# UV_MONITOR_V2.net
KiCad netlist of a schematic drawn in EAGLE
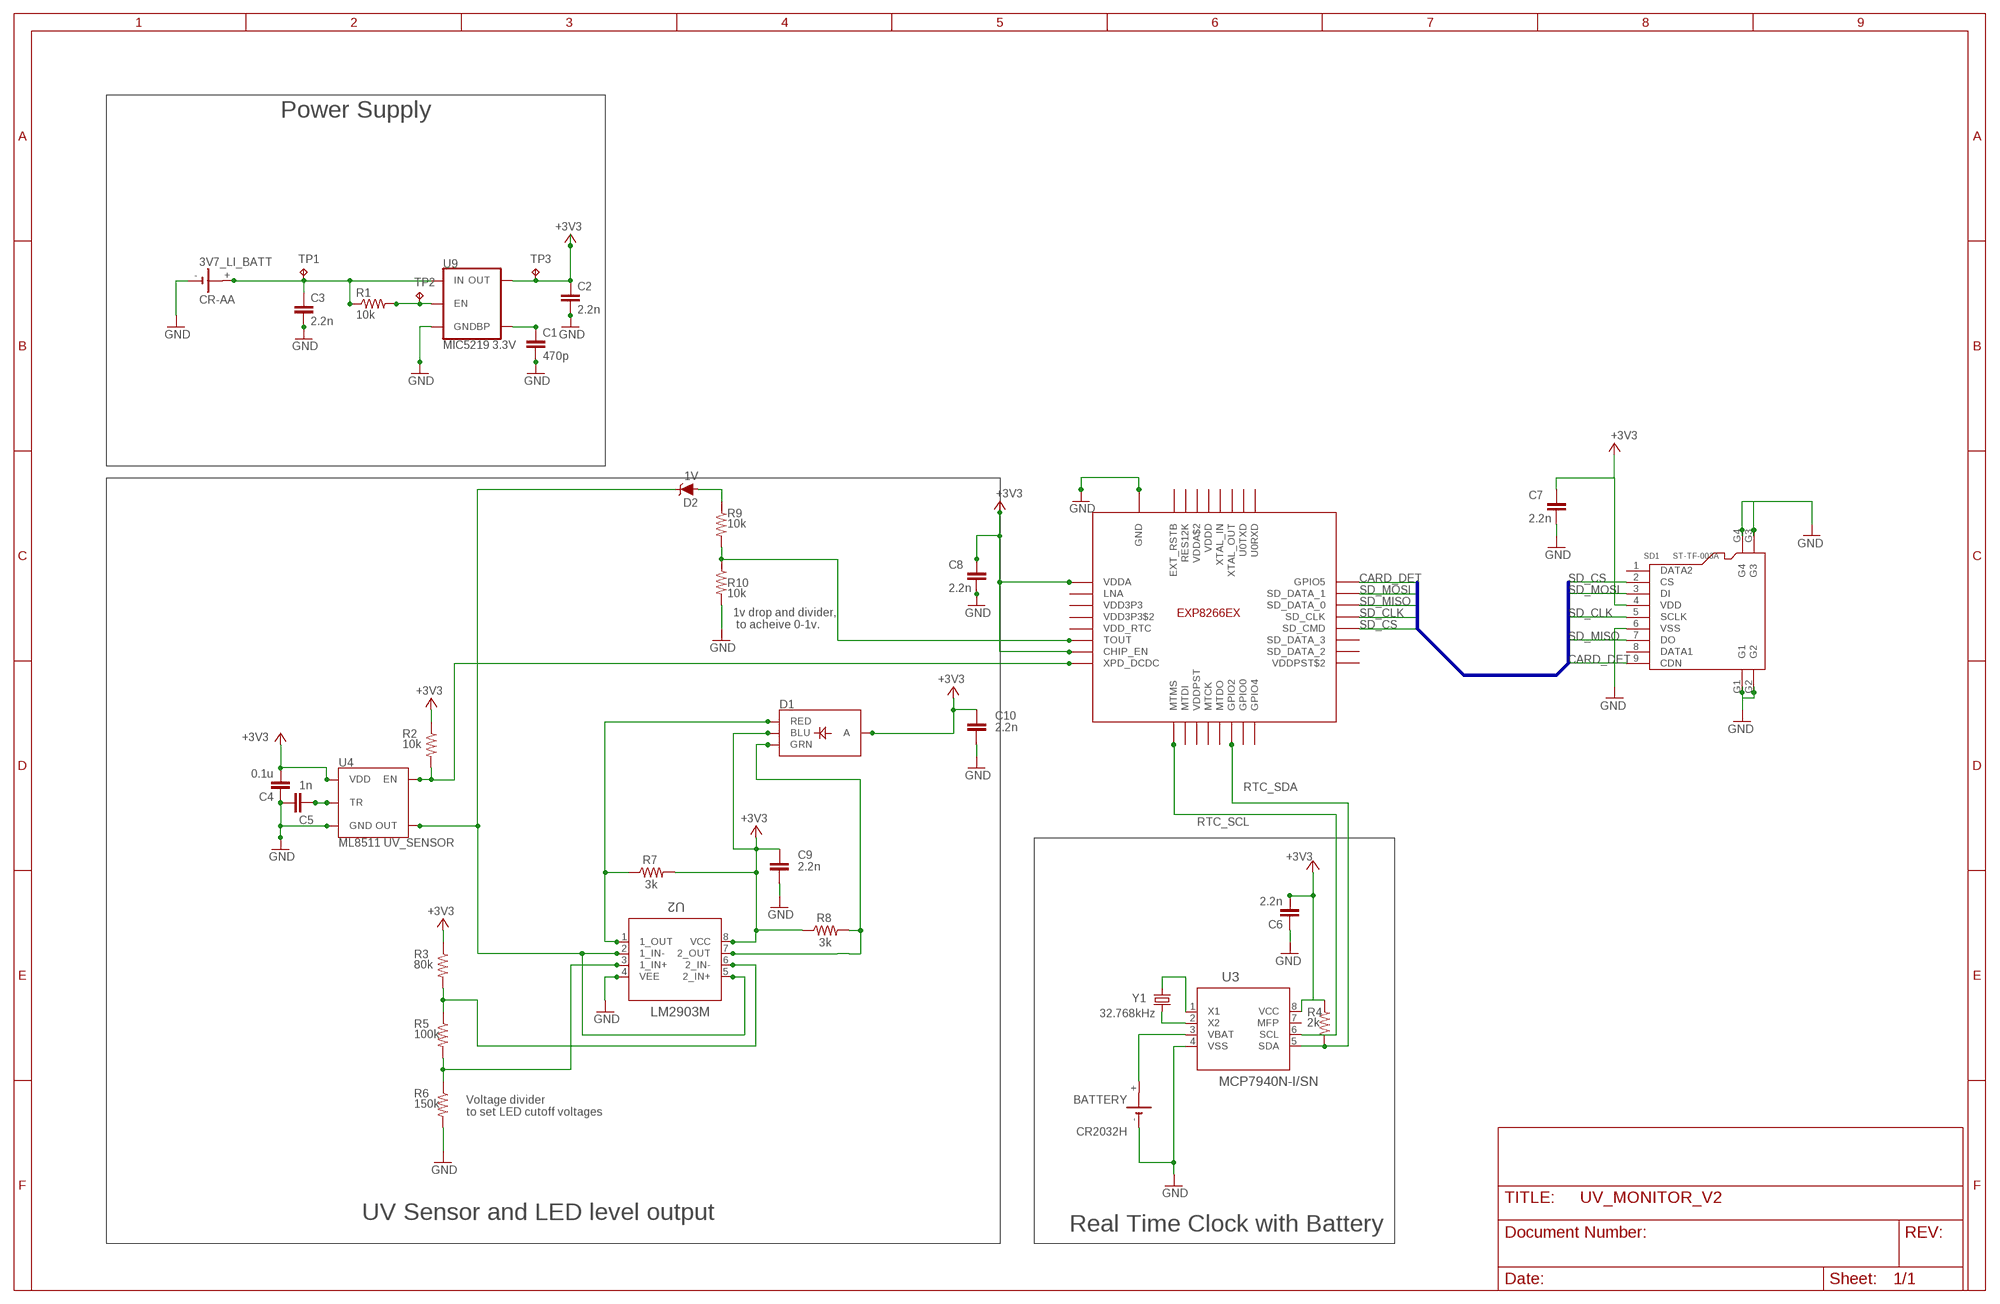
[diagram p0: schematic, sheet 1]

(export (version "E")
  (design (tool "Eeschema 10.0.6"))
  (components
    (comp (ref "3V7_LI_BATT")
      (value "CR-AA")
      (footprint "eagle-import:CRAA")
      (libsource (lib "eagle-import") (part "CR-AA"))
    )
    (comp (ref "BATTERY")
      (value "CR2032H")
      (footprint "eagle-import:CR2032H")
      (libsource (lib "eagle-import") (part "CR2032H"))
    )
    (comp (ref "C1")
      (value "470p")
      (footprint "eagle-import:C0805")
      (libsource (lib "eagle-import") (part "C-EUC0805"))
    )
    (comp (ref "C2")
      (value "2.2n")
      (footprint "eagle-import:C0805")
      (libsource (lib "eagle-import") (part "C-EUC0805"))
    )
    (comp (ref "C3")
      (value "2.2n")
      (footprint "eagle-import:C0805")
      (libsource (lib "eagle-import") (part "C-EUC0805"))
    )
    (comp (ref "C4")
      (value "0.1u")
      (footprint "eagle-import:C0805")
      (libsource (lib "eagle-import") (part "C-EUC0805"))
    )
    (comp (ref "C5")
      (value "1n")
      (footprint "eagle-import:C0805")
      (libsource (lib "eagle-import") (part "C-EUC0805"))
    )
    (comp (ref "C6")
      (value "2.2n")
      (footprint "eagle-import:C0805")
      (libsource (lib "eagle-import") (part "C-EUC0805"))
    )
    (comp (ref "C7")
      (value "2.2n")
      (footprint "eagle-import:C0805")
      (libsource (lib "eagle-import") (part "C-EUC0805"))
    )
    (comp (ref "C8")
      (value "2.2n")
      (footprint "eagle-import:C0805")
      (libsource (lib "eagle-import") (part "C-EUC0805"))
    )
    (comp (ref "C9")
      (value "2.2n")
      (footprint "eagle-import:C0805")
      (libsource (lib "eagle-import") (part "C-EUC0805"))
    )
    (comp (ref "C10")
      (value "2.2n")
      (footprint "eagle-import:C0805")
      (libsource (lib "eagle-import") (part "C-EUC0805"))
    )
    (comp (ref "D1")
      (value "LED-RGB-CASMD")
      (footprint "eagle-import:LED-TRICOLOR-SMD")
      (libsource (lib "eagle-import") (part "LED-RGB-CASMD"))
    )
    (comp (ref "D2")
      (value "1V")
      (footprint "eagle-import:SOD-323")
      (libsource (lib "eagle-import") (part "DIODE-ZENER-BZT52C3V6S"))
    )
    (comp (ref "R1")
      (value "10k")
      (footprint "eagle-import:R0805")
      (libsource (lib "eagle-import") (part "R-US_R0805"))
    )
    (comp (ref "R2")
      (value "10k")
      (footprint "eagle-import:R0805")
      (libsource (lib "eagle-import") (part "R-US_R0805"))
    )
    (comp (ref "R3")
      (value "80k")
      (footprint "eagle-import:R0805")
      (libsource (lib "eagle-import") (part "R-US_R0805"))
    )
    (comp (ref "R4")
      (value "2k")
      (footprint "eagle-import:R0805")
      (libsource (lib "eagle-import") (part "R-US_R0805"))
    )
    (comp (ref "R5")
      (value "100k")
      (footprint "eagle-import:R0805")
      (libsource (lib "eagle-import") (part "R-US_R0805"))
    )
    (comp (ref "R6")
      (value "150k")
      (footprint "eagle-import:R0805")
      (libsource (lib "eagle-import") (part "R-US_R0805"))
    )
    (comp (ref "R7")
      (value "3k")
      (footprint "eagle-import:R0805")
      (libsource (lib "eagle-import") (part "R-US_R0805"))
    )
    (comp (ref "R8")
      (value "3k")
      (footprint "eagle-import:R0805")
      (libsource (lib "eagle-import") (part "R-US_R0805"))
    )
    (comp (ref "R9")
      (value "10k")
      (footprint "eagle-import:R0805")
      (libsource (lib "eagle-import") (part "R-US_R0805"))
    )
    (comp (ref "R10")
      (value "10k")
      (footprint "eagle-import:R0805")
      (libsource (lib "eagle-import") (part "R-US_R0805"))
    )
    (comp (ref "SD1")
      (value "ST-TF-003A")
      (footprint "eagle-import:MICRO-SD9+4P-SMD-16.1X14.5X1.85MM")
      (libsource (lib "eagle-import") (part "MICRO-SD-CARD-SOCKET-9P(ST-TF-003A)"))
    )
    (comp (ref "TP1")
      (value "TPPAD1-13")
      (footprint "eagle-import:P1-13")
      (libsource (lib "eagle-import") (part "TPPAD1-13"))
    )
    (comp (ref "TP2")
      (value "TPPAD1-13")
      (footprint "eagle-import:P1-13")
      (libsource (lib "eagle-import") (part "TPPAD1-13"))
    )
    (comp (ref "TP3")
      (value "TPPAD1-13")
      (footprint "eagle-import:P1-13")
      (libsource (lib "eagle-import") (part "TPPAD1-13"))
    )
    (comp (ref "U1")
      (value "ESP8266EX")
      (footprint "eagle-import:ESP8266EX")
      (libsource (lib "eagle-import") (part "ESP8266EX"))
    )
    (comp (ref "U2")
      (value "LM2903M")
      (footprint "eagle-import:M08A")
      (libsource (lib "eagle-import") (part "LM2903M"))
    )
    (comp (ref "U3")
      (value "MCP7940N-I/SN")
      (footprint "eagle-import:SOIC8-N_MC")
      (fields (field (name "MANUFACTURER_PART_NUMBER") "MCP7940NISN"))
      (libsource (lib "eagle-import") (part "MCP7940N-I/SN"))
    )
    (comp (ref "U4")
      (value "ML8511 UV_SENSOR")
      (footprint "eagle-import:ML8511")
      (libsource (lib "eagle-import") (part "ML8511"))
    )
    (comp (ref "U9")
      (value "MIC5219 3.3V")
      (footprint "eagle-import:SOT23-5")
      (libsource (lib "eagle-import") (part "V_REG_MIC52193.3V"))
    )
    (comp (ref "Y1")
      (value "32.768kHz")
      (footprint "eagle-import:CRYSTAL-SMD-2X6-CYL")
      (libsource (lib "eagle-import") (part "CRYSTAL-32.768KHZSMD-2X6"))
    )
  )
  (nets
    (net (code "1") (name "+3V3") (class "Default")
      (node (ref "C10") (pin "1") (pinfunction "1_1") (pintype "passive"))
      (node (ref "C2") (pin "1") (pinfunction "1_1") (pintype "passive"))
      (node (ref "C4") (pin "2") (pinfunction "2_2") (pintype "passive"))
      (node (ref "C6") (pin "2") (pinfunction "2_2") (pintype "passive"))
      (node (ref "C7") (pin "1") (pinfunction "1_1") (pintype "passive"))
      (node (ref "C8") (pin "1") (pinfunction "1_1") (pintype "passive"))
      (node (ref "C9") (pin "1") (pinfunction "1_1") (pintype "passive"))
      (node (ref "D1") (pin "A") (pinfunction "A_A") (pintype "bidirectional"))
      (node (ref "D1") (pin "B") (pinfunction "BLU_B") (pintype "bidirectional"))
      (node (ref "R2") (pin "1") (pinfunction "1_1") (pintype "passive"))
      (node (ref "R3") (pin "1") (pinfunction "1_1") (pintype "passive"))
      (node (ref "R4") (pin "1") (pinfunction "1_1") (pintype "passive"))
      (node (ref "R7") (pin "2") (pinfunction "2_2") (pintype "passive"))
      (node (ref "R8") (pin "1") (pinfunction "1_1") (pintype "passive"))
      (node (ref "SD1") (pin "4") (pinfunction "VDD_4") (pintype "bidirectional"))
      (node (ref "TP3") (pin "TP") (pinfunction "TP_TP") (pintype "input"))
      (node (ref "U1") (pin "CHIP_EN") (pinfunction "CHIP_EN_CHIP_EN") (pintype "bidirectional"))
      (node (ref "U1") (pin "VDDA") (pinfunction "VDDA_VDDA") (pintype "bidirectional"))
      (node (ref "U2") (pin "8") (pinfunction "VCC_8") (pintype "passive"))
      (node (ref "U3") (pin "8") (pinfunction "VCC_8") (pintype "power_in"))
      (node (ref "U4") (pin "7") (pinfunction "VDD_7") (pintype "power_in"))
      (node (ref "U9") (pin "5") (pinfunction "OUT_5") (pintype "passive"))
    )
    (net (code "2") (name "/CARD_DET") (class "Default")
      (node (ref "SD1") (pin "9") (pinfunction "CDN_9") (pintype "bidirectional"))
      (node (ref "U1") (pin "GPOIO5") (pinfunction "GPIO5_GPOIO5") (pintype "bidirectional"))
    )
    (net (code "3") (name "/RTC_SCL") (class "Default")
      (node (ref "U1") (pin "MTMS") (pinfunction "MTMS_MTMS") (pintype "bidirectional"))
      (node (ref "U3") (pin "6") (pinfunction "SCL_6") (pintype "passive"))
    )
    (net (code "4") (name "/RTC_SDA") (class "Default")
      (node (ref "R4") (pin "2") (pinfunction "2_2") (pintype "passive"))
      (node (ref "U1") (pin "GPIO2") (pinfunction "GPIO2_GPIO2") (pintype "bidirectional"))
      (node (ref "U3") (pin "5") (pinfunction "SDA_5") (pintype "bidirectional"))
    )
    (net (code "5") (name "/SD_CLK") (class "Default")
      (node (ref "SD1") (pin "5") (pinfunction "SCLK_5") (pintype "bidirectional"))
      (node (ref "U1") (pin "SD_CLK") (pinfunction "SD_CLK_SD_CLK") (pintype "bidirectional"))
    )
    (net (code "6") (name "/SD_CS") (class "Default")
      (node (ref "SD1") (pin "2") (pinfunction "CS_2") (pintype "bidirectional"))
      (node (ref "U1") (pin "SD_CMD") (pinfunction "SD_CMD_SD_CMD") (pintype "bidirectional"))
    )
    (net (code "7") (name "/SD_MISO") (class "Default")
      (node (ref "SD1") (pin "7") (pinfunction "DO_7") (pintype "bidirectional"))
      (node (ref "U1") (pin "SD_DATA_0") (pinfunction "SD_DATA_0_SD_DATA_0") (pintype "bidirectional"))
    )
    (net (code "8") (name "/SD_MOSI") (class "Default")
      (node (ref "SD1") (pin "3") (pinfunction "DI_3") (pintype "bidirectional"))
      (node (ref "U1") (pin "SD_DATA_1") (pinfunction "SD_DATA_1_SD_DATA_1") (pintype "bidirectional"))
    )
    (net (code "9") (name "GND") (class "Default")
      (node (ref "3V7_LI_BATT") (pin "-") (pinfunction "-_-") (pintype "passive"))
      (node (ref "BATTERY") (pin "-") (pinfunction "-_-") (pintype "passive"))
      (node (ref "C1") (pin "2") (pinfunction "2_2") (pintype "passive"))
      (node (ref "C10") (pin "2") (pinfunction "2_2") (pintype "passive"))
      (node (ref "C2") (pin "2") (pinfunction "2_2") (pintype "passive"))
      (node (ref "C3") (pin "2") (pinfunction "2_2") (pintype "passive"))
      (node (ref "C4") (pin "1") (pinfunction "1_1") (pintype "passive"))
      (node (ref "C5") (pin "2") (pinfunction "2_2") (pintype "passive"))
      (node (ref "C6") (pin "1") (pinfunction "1_1") (pintype "passive"))
      (node (ref "C7") (pin "2") (pinfunction "2_2") (pintype "passive"))
      (node (ref "C8") (pin "2") (pinfunction "2_2") (pintype "passive"))
      (node (ref "C9") (pin "2") (pinfunction "2_2") (pintype "passive"))
      (node (ref "R10") (pin "2") (pinfunction "2_2") (pintype "passive"))
      (node (ref "R6") (pin "2") (pinfunction "2_2") (pintype "passive"))
      (node (ref "SD1") (pin "6") (pinfunction "VSS_6") (pintype "bidirectional"))
      (node (ref "SD1") (pin "G1") (pinfunction "G1_G1") (pintype "bidirectional"))
      (node (ref "SD1") (pin "G2") (pinfunction "G2_G2") (pintype "bidirectional"))
      (node (ref "SD1") (pin "G3") (pinfunction "G3_G3") (pintype "bidirectional"))
      (node (ref "SD1") (pin "G4") (pinfunction "G4_G4") (pintype "bidirectional"))
      (node (ref "U1") (pin "GND") (pinfunction "GND_GND") (pintype "bidirectional"))
      (node (ref "U2") (pin "4") (pinfunction "VEE_4") (pintype "passive"))
      (node (ref "U3") (pin "4") (pinfunction "VSS_4") (pintype "power_in"))
      (node (ref "U4") (pin "5") (pinfunction "GND_5") (pintype "power_in"))
      (node (ref "U9") (pin "2") (pinfunction "GND_2") (pintype "input"))
    )
    (net (code "10") (name "Net-(D1-GRN)") (class "Default")
      (node (ref "D1") (pin "G") (pinfunction "GRN_G") (pintype "bidirectional"))
      (node (ref "R8") (pin "2") (pinfunction "2_2") (pintype "passive"))
      (node (ref "U2") (pin "7") (pinfunction "2_OUT_7") (pintype "passive"))
    )
    (net (code "11") (name "Net-(D1-RED)") (class "Default")
      (node (ref "D1") (pin "R") (pinfunction "RED_R") (pintype "bidirectional"))
      (node (ref "R7") (pin "1") (pinfunction "1_1") (pintype "passive"))
      (node (ref "U2") (pin "1") (pinfunction "1_OUT_1") (pintype "passive"))
    )
    (net (code "12") (name "Net-(D2-PadA)") (class "Default")
      (node (ref "D2") (pin "A") (pinfunction "A_A") (pintype "passive"))
      (node (ref "R9") (pin "1") (pinfunction "1_1") (pintype "passive"))
    )
    (net (code "13") (name "Net-(R10-Pad1)") (class "Default")
      (node (ref "R10") (pin "1") (pinfunction "1_1") (pintype "passive"))
      (node (ref "R9") (pin "2") (pinfunction "2_2") (pintype "passive"))
      (node (ref "U1") (pin "TOUT") (pinfunction "TOUT_TOUT") (pintype "bidirectional"))
    )
    (net (code "14") (name "Net-(U2-1_IN+)") (class "Default")
      (node (ref "R5") (pin "2") (pinfunction "2_2") (pintype "passive"))
      (node (ref "R6") (pin "1") (pinfunction "1_1") (pintype "passive"))
      (node (ref "U2") (pin "3") (pinfunction "1_IN+_3") (pintype "passive"))
    )
    (net (code "15") (name "Net-(U2-1_IN-)") (class "Default")
      (node (ref "D2") (pin "C") (pinfunction "C_C") (pintype "passive"))
      (node (ref "U2") (pin "2") (pinfunction "1_IN-_2") (pintype "passive"))
      (node (ref "U2") (pin "5") (pinfunction "2_IN+_5") (pintype "passive"))
      (node (ref "U4") (pin "8") (pinfunction "OUT_8") (pintype "output"))
    )
    (net (code "16") (name "Net-(U2-2_IN-)") (class "Default")
      (node (ref "R3") (pin "2") (pinfunction "2_2") (pintype "passive"))
      (node (ref "R5") (pin "1") (pinfunction "1_1") (pintype "passive"))
      (node (ref "U2") (pin "6") (pinfunction "2_IN-_6") (pintype "passive"))
    )
    (net (code "17") (name "Net-(U3-VBAT)") (class "Default")
      (node (ref "BATTERY") (pin "+") (pinfunction "+_+") (pintype "passive"))
      (node (ref "U3") (pin "3") (pinfunction "VBAT_3") (pintype "power_in"))
    )
    (net (code "18") (name "Net-(U3-X1)") (class "Default")
      (node (ref "U3") (pin "1") (pinfunction "X1_1") (pintype "input"))
      (node (ref "Y1") (pin "X1") (pinfunction "1_X1") (pintype "passive"))
    )
    (net (code "19") (name "Net-(U3-X2)") (class "Default")
      (node (ref "U3") (pin "2") (pinfunction "X2_2") (pintype "output"))
      (node (ref "Y1") (pin "X2") (pinfunction "2_X2") (pintype "passive"))
    )
    (net (code "20") (name "Net-(U4-EN)") (class "Default")
      (node (ref "R2") (pin "2") (pinfunction "2_2") (pintype "passive"))
      (node (ref "U1") (pin "XPD_DCDC") (pinfunction "XPD_DCDC_XPD_DCDC") (pintype "bidirectional"))
      (node (ref "U4") (pin "4") (pinfunction "EN_4") (pintype "input"))
    )
    (net (code "21") (name "Net-(U4-TR)") (class "Default")
      (node (ref "C5") (pin "1") (pinfunction "1_1") (pintype "passive"))
      (node (ref "U4") (pin "10") (pinfunction "TR_10") (pintype "power_in"))
    )
    (net (code "22") (name "Net-(U9-BP)") (class "Default")
      (node (ref "C1") (pin "1") (pinfunction "1_1") (pintype "passive"))
      (node (ref "U9") (pin "4") (pinfunction "BP_4") (pintype "input"))
    )
    (net (code "23") (name "Net-(U9-EN)") (class "Default")
      (node (ref "R1") (pin "2") (pinfunction "2_2") (pintype "passive"))
      (node (ref "TP2") (pin "TP") (pinfunction "TP_TP") (pintype "input"))
      (node (ref "U9") (pin "3") (pinfunction "EN_3") (pintype "input"))
    )
    (net (code "24") (name "Net-(U9-IN)") (class "Default")
      (node (ref "3V7_LI_BATT") (pin "+") (pinfunction "+_+") (pintype "passive"))
      (node (ref "C3") (pin "1") (pinfunction "1_1") (pintype "passive"))
      (node (ref "R1") (pin "1") (pinfunction "1_1") (pintype "passive"))
      (node (ref "TP1") (pin "TP") (pinfunction "TP_TP") (pintype "input"))
      (node (ref "U9") (pin "1") (pinfunction "IN_1") (pintype "input"))
    )
    (net (code "25") (name "unconnected-(3V7_LI_BATT-+-Pad+@1)") (class "Default")
      (node (ref "3V7_LI_BATT") (pin "+@1") (pinfunction "+_+@1") (pintype "passive"))
    )
    (net (code "26") (name "unconnected-(BATTERY-+-Pad+@1)") (class "Default")
      (node (ref "BATTERY") (pin "+@1") (pinfunction "+_+@1") (pintype "passive"))
    )
    (net (code "27") (name "unconnected-(SD1-DATA1-Pad8)") (class "Default")
      (node (ref "SD1") (pin "8") (pinfunction "DATA1_8") (pintype "bidirectional"))
    )
    (net (code "28") (name "unconnected-(SD1-DATA2-Pad1)") (class "Default")
      (node (ref "SD1") (pin "1") (pinfunction "DATA2_1") (pintype "bidirectional"))
    )
    (net (code "29") (name "unconnected-(U1-PadEXT_RSTB)") (class "Default")
      (node (ref "U1") (pin "EXT_RSTB") (pinfunction "EXT_RSTB_EXT_RSTB") (pintype "bidirectional"))
    )
    (net (code "30") (name "unconnected-(U1-PadGPIO0)") (class "Default")
      (node (ref "U1") (pin "GPIO0") (pinfunction "GPIO0_GPIO0") (pintype "bidirectional"))
    )
    (net (code "31") (name "unconnected-(U1-PadGPIO4)") (class "Default")
      (node (ref "U1") (pin "GPIO4") (pinfunction "GPIO4_GPIO4") (pintype "bidirectional"))
    )
    (net (code "32") (name "unconnected-(U1-PadLNA)") (class "Default")
      (node (ref "U1") (pin "LNA") (pinfunction "LNA_LNA") (pintype "bidirectional"))
    )
    (net (code "33") (name "unconnected-(U1-PadMTCK)") (class "Default")
      (node (ref "U1") (pin "MTCK") (pinfunction "MTCK_MTCK") (pintype "bidirectional"))
    )
    (net (code "34") (name "unconnected-(U1-PadMTDI)") (class "Default")
      (node (ref "U1") (pin "MTDI") (pinfunction "MTDI_MTDI") (pintype "bidirectional"))
    )
    (net (code "35") (name "unconnected-(U1-PadMTDO)") (class "Default")
      (node (ref "U1") (pin "MTDO") (pinfunction "MTDO_MTDO") (pintype "bidirectional"))
    )
    (net (code "36") (name "unconnected-(U1-PadRES12K)") (class "Default")
      (node (ref "U1") (pin "RES12K") (pinfunction "RES12K_RES12K") (pintype "bidirectional"))
    )
    (net (code "37") (name "unconnected-(U1-PadSD_DATA_2)") (class "Default")
      (node (ref "U1") (pin "SD_DATA_2") (pinfunction "SD_DATA_2_SD_DATA_2") (pintype "bidirectional"))
    )
    (net (code "38") (name "unconnected-(U1-PadSD_DATA_3)") (class "Default")
      (node (ref "U1") (pin "SD_DATA_3") (pinfunction "SD_DATA_3_SD_DATA_3") (pintype "bidirectional"))
    )
    (net (code "39") (name "unconnected-(U1-PadU0RXD)") (class "Default")
      (node (ref "U1") (pin "U0RXD") (pinfunction "U0RXD_U0RXD") (pintype "bidirectional"))
    )
    (net (code "40") (name "unconnected-(U1-PadU0TXD)") (class "Default")
      (node (ref "U1") (pin "U0TXD") (pinfunction "U0TXD_U0TXD") (pintype "bidirectional"))
    )
    (net (code "41") (name "unconnected-(U1-PadVDD3P3$2)") (class "Default")
      (node (ref "U1") (pin "VDD3P3$2") (pinfunction "VDD3P3$2_VDD3P3$2") (pintype "bidirectional"))
    )
    (net (code "42") (name "unconnected-(U1-PadVDD3P3)") (class "Default")
      (node (ref "U1") (pin "VDD3P3") (pinfunction "VDD3P3_VDD3P3") (pintype "bidirectional"))
    )
    (net (code "43") (name "unconnected-(U1-PadVDDA$2)") (class "Default")
      (node (ref "U1") (pin "VDDA$2") (pinfunction "VDDA$2_VDDA$2") (pintype "bidirectional"))
    )
    (net (code "44") (name "unconnected-(U1-PadVDDD)") (class "Default")
      (node (ref "U1") (pin "VDDD") (pinfunction "VDDD_VDDD") (pintype "bidirectional"))
    )
    (net (code "45") (name "unconnected-(U1-PadVDDPST$2)") (class "Default")
      (node (ref "U1") (pin "VDDPST$2") (pinfunction "VDDPST$2_VDDPST$2") (pintype "bidirectional"))
    )
    (net (code "46") (name "unconnected-(U1-PadVDDPST)") (class "Default")
      (node (ref "U1") (pin "VDDPST") (pinfunction "VDDPST_VDDPST") (pintype "bidirectional"))
    )
    (net (code "47") (name "unconnected-(U1-PadVDD_RTC)") (class "Default")
      (node (ref "U1") (pin "VDD_RTC") (pinfunction "VDD_RTC_VDD_RTC") (pintype "bidirectional"))
    )
    (net (code "48") (name "unconnected-(U1-PadXTAL_IN)") (class "Default")
      (node (ref "U1") (pin "XTAL_IN") (pinfunction "XTAL_IN_XTAL_IN") (pintype "bidirectional"))
    )
    (net (code "49") (name "unconnected-(U1-PadXTAL_OUT)") (class "Default")
      (node (ref "U1") (pin "XTAL_OUT") (pinfunction "XTAL_OUT_XTAL_OUT") (pintype "bidirectional"))
    )
    (net (code "50") (name "unconnected-(U3-MFP-Pad7)") (class "Default")
      (node (ref "U3") (pin "7") (pinfunction "MFP_7") (pintype "passive"))
    )
  )
)
